# 1-Schematic_Hardware_Space_Systems.net
KiCad netlist of a schematic drawn in EasyEDA
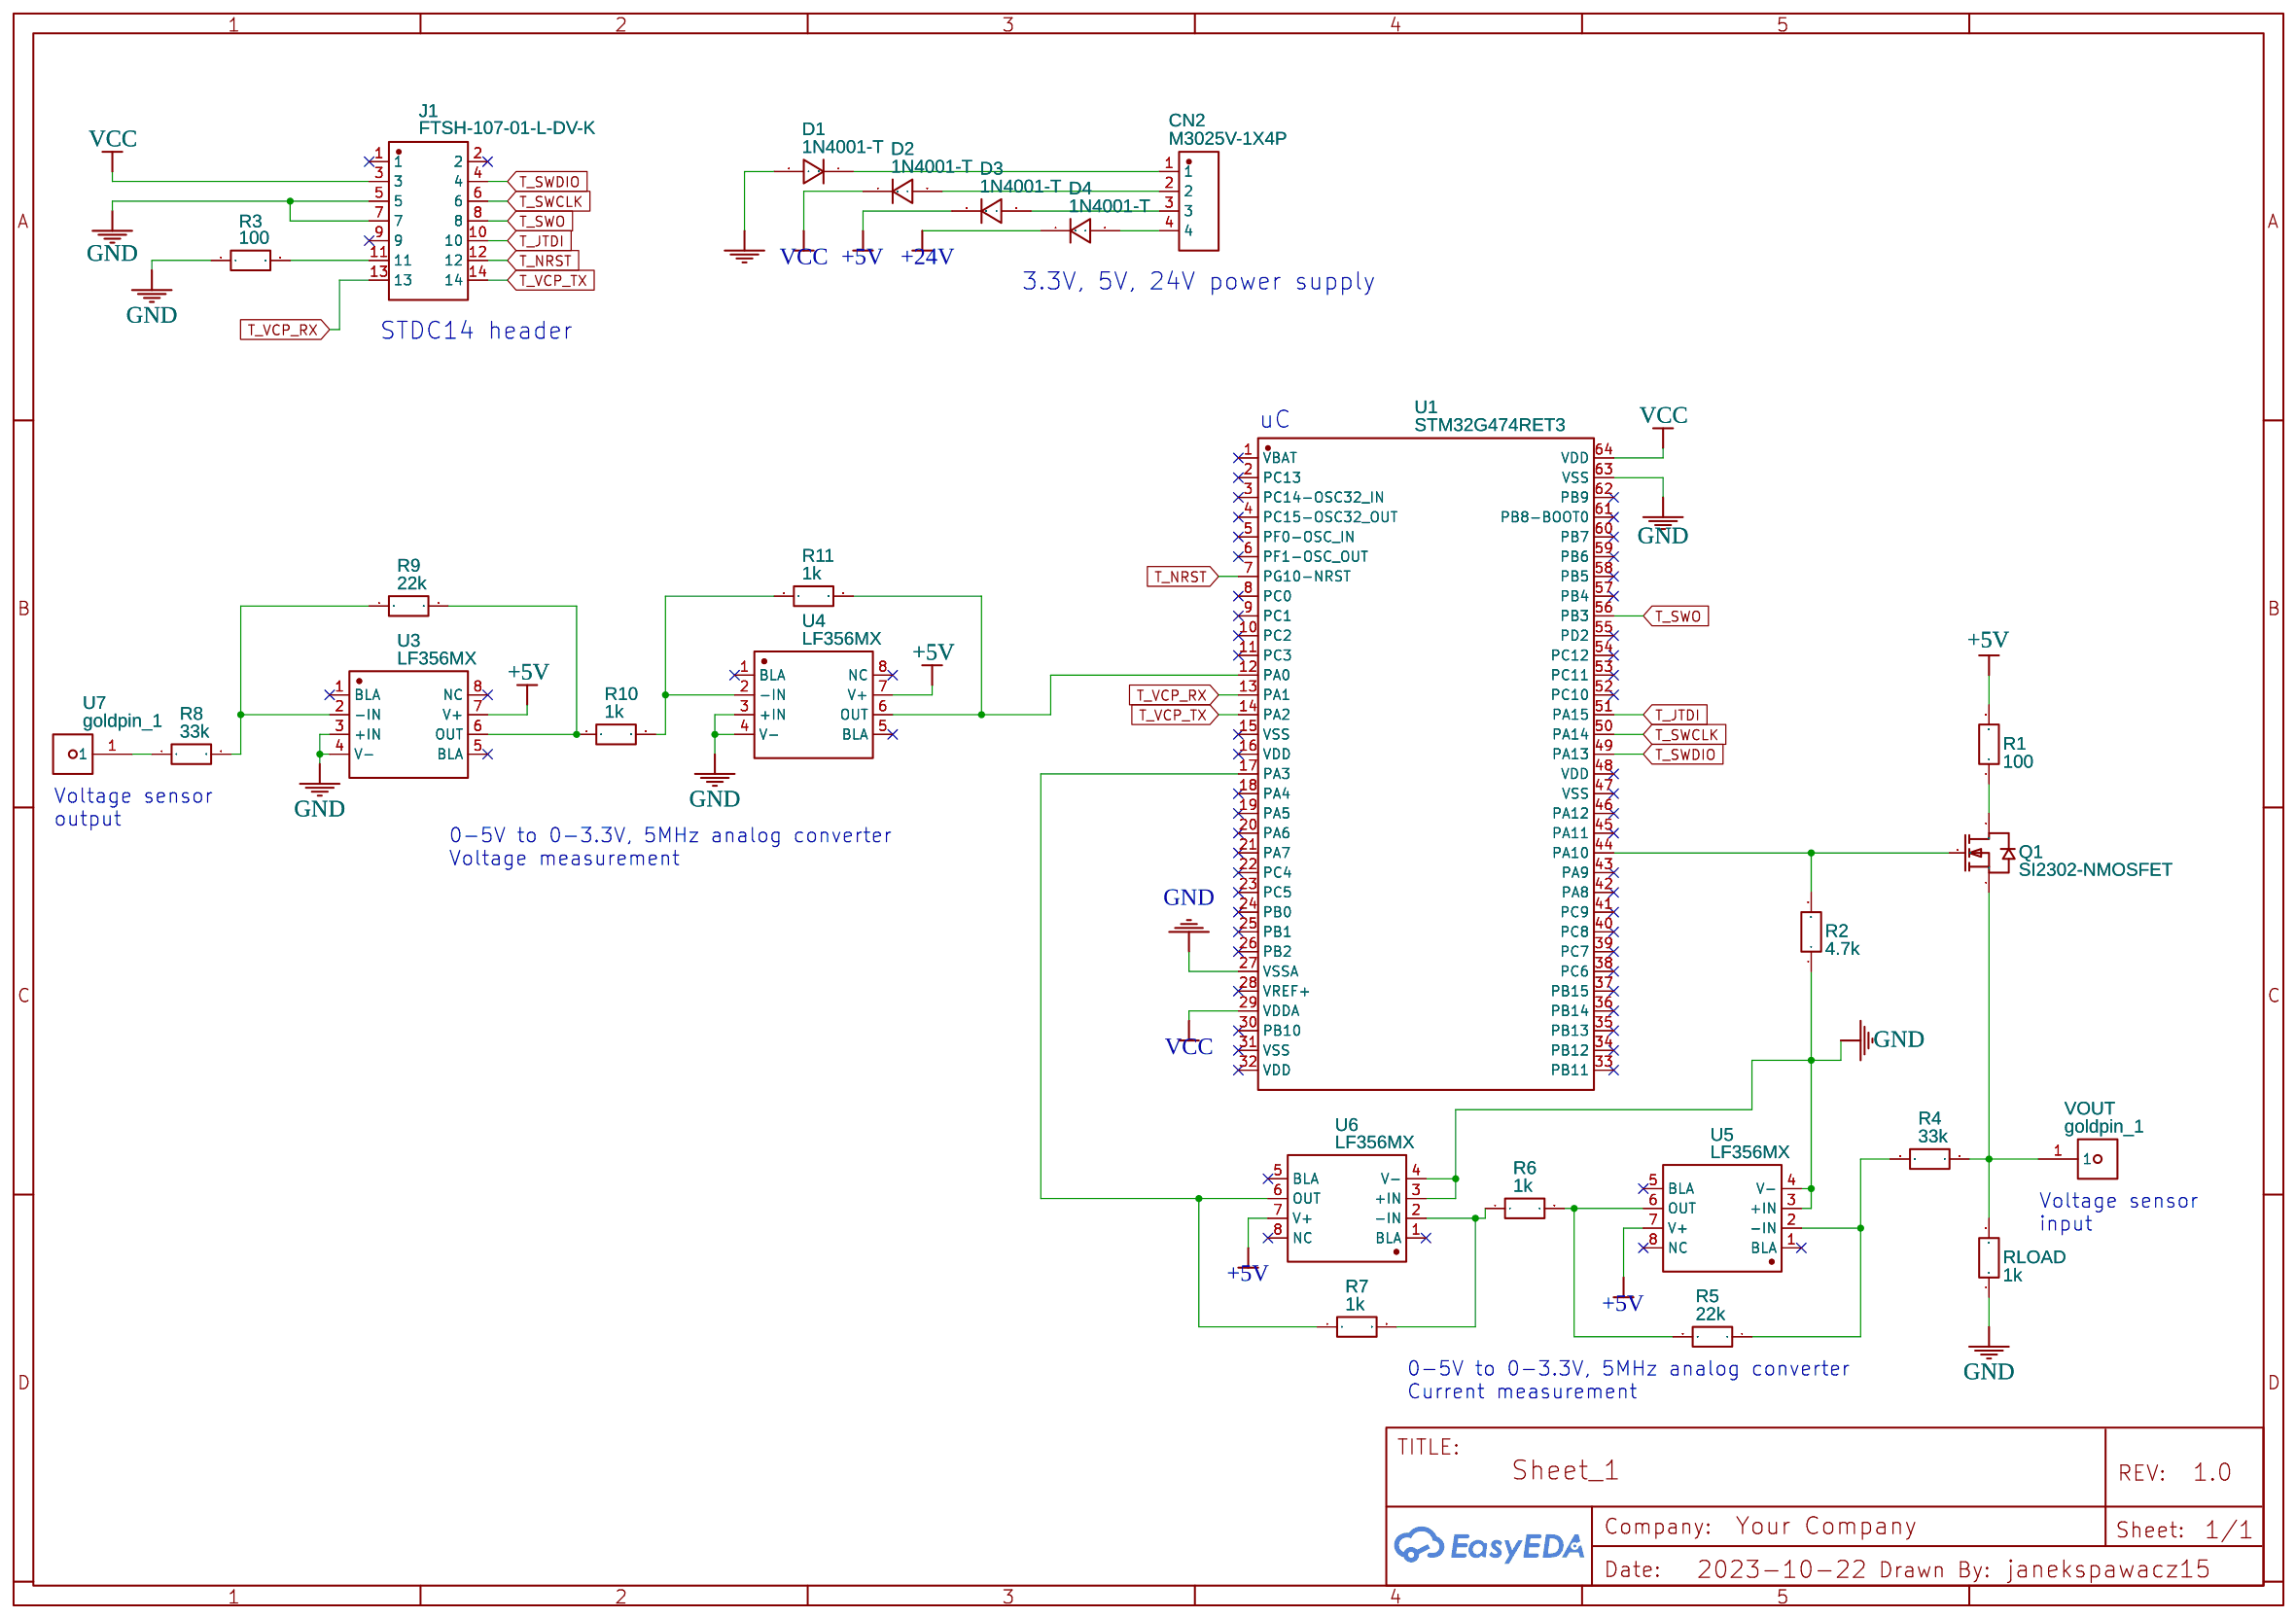
[diagram p0: schematic sheet]

(export (version "E")
  (design (tool "Eeschema 10.0.6"))
  (components
    (comp (ref "CN2")
      (value "M3025V-1X4P")
      (fields (field (name "Manufacturer Part") "M3025V-1x4P") (field (name "Manufacturer") "XFCN(台湾兴飞)"))
      (libsource (lib "") (part "M3025V-1X4P"))
    )
    (comp (ref "D1")
      (value "1N4001-T")
      (fields (field (name "Manufacturer") "DIODES(美台)"))
      (libsource (lib "") (part "1N4001-T_1"))
    )
    (comp (ref "D2")
      (value "1N4001-T")
      (fields (field (name "Manufacturer") "DIODES(美台)"))
      (libsource (lib "") (part "1N4001-T"))
    )
    (comp (ref "D3")
      (value "1N4001-T")
      (fields (field (name "Manufacturer") "DIODES(美台)"))
      (libsource (lib "") (part "1N4001-T"))
    )
    (comp (ref "D4")
      (value "1N4001-T")
      (fields (field (name "Manufacturer") "DIODES(美台)"))
      (libsource (lib "") (part "1N4001-T"))
    )
    (comp (ref "J1")
      (value "FTSH-107-01-L-DV-K")
      (fields (field (name "Manufacturer") "Samtec"))
      (libsource (lib "") (part "FTSH-107-01-L-DV-K"))
    )
    (comp (ref "Q1")
      (value "SI2302-NMOSFET")
      (fields (field (name "Manufacturer Part") "si2302-nmosfet"))
      (libsource (lib "") (part "SI2302-NMOSFET"))
    )
    (comp (ref "R1") (value "100") (libsource (lib "") (part "R_0603_EU_3")))
    (comp (ref "R2") (value "4.7k") (libsource (lib "") (part "R_0603_EU_3")))
    (comp (ref "R3") (value "100") (libsource (lib "") (part "R_0603_EU_1")))
    (comp (ref "R4") (value "33k") (libsource (lib "") (part "R_0603_EU_2")))
    (comp (ref "R5") (value "22k") (libsource (lib "") (part "R_0603_EU_2")))
    (comp (ref "R6") (value "1k") (libsource (lib "") (part "R_0603_EU_1")))
    (comp (ref "R7") (value "1k") (libsource (lib "") (part "R_0603_EU_1")))
    (comp (ref "R8") (value "33k") (libsource (lib "") (part "R_0603_EU_1")))
    (comp (ref "R9") (value "22k") (libsource (lib "") (part "R_0603_EU_1")))
    (comp (ref "R10") (value "1k") (libsource (lib "") (part "R_0603_EU_1")))
    (comp (ref "R11") (value "1k") (libsource (lib "") (part "R_0603_EU_1")))
    (comp (ref "RLOAD") (value "1k") (libsource (lib "") (part "R_0603_EU")))
    (comp (ref "U1")
      (value "STM32G474RET3")
      (fields (field (name "Manufacturer") "ST(意法半导体)"))
      (libsource (lib "") (part "STM32G474RET3"))
    )
    (comp (ref "U3")
      (value "LF356MX")
      (fields (field (name "Manufacturer Part") "LF356MX/NOPB") (field (name "Manufacturer") "TI(德州仪器)"))
      (libsource (lib "") (part "LF356MX"))
    )
    (comp (ref "U4")
      (value "LF356MX")
      (fields (field (name "Manufacturer Part") "LF356MX/NOPB") (field (name "Manufacturer") "TI(德州仪器)"))
      (libsource (lib "") (part "LF356MX"))
    )
    (comp (ref "U5")
      (value "LF356MX")
      (fields (field (name "Manufacturer Part") "LF356MX/NOPB") (field (name "Manufacturer") "TI(德州仪器)"))
      (libsource (lib "") (part "LF356MX_1"))
    )
    (comp (ref "U6")
      (value "LF356MX")
      (fields (field (name "Manufacturer Part") "LF356MX/NOPB") (field (name "Manufacturer") "TI(德州仪器)"))
      (libsource (lib "") (part "LF356MX_1"))
    )
    (comp (ref "U7") (value "goldpin_1") (libsource (lib "") (part "goldpin_1_1")))
    (comp (ref "VOUT") (value "goldpin_1") (libsource (lib "") (part "goldpin_1")))
  )
  (nets
    (net (code "1") (name "+5V") (class "Default")
      (node (ref "D3") (pin "1") (pinfunction "C_1") (pintype "unspecified"))
      (node (ref "R1") (pin "2") (pinfunction "2_2") (pintype "unspecified"))
      (node (ref "U3") (pin "7") (pinfunction "V+_7") (pintype "unspecified"))
      (node (ref "U4") (pin "7") (pinfunction "V+_7") (pintype "unspecified"))
      (node (ref "U5") (pin "7") (pinfunction "V+_7") (pintype "unspecified"))
      (node (ref "U6") (pin "7") (pinfunction "V+_7") (pintype "unspecified"))
    )
    (net (code "2") (name "+24V") (class "Default")
      (node (ref "D4") (pin "1") (pinfunction "C_1") (pintype "unspecified"))
    )
    (net (code "3") (name "GND") (class "Default")
      (node (ref "D1") (pin "2") (pinfunction "A_2") (pintype "unspecified"))
      (node (ref "J1") (pin "5") (pinfunction "5_5") (pintype "unspecified"))
      (node (ref "J1") (pin "7") (pinfunction "7_7") (pintype "unspecified"))
      (node (ref "R2") (pin "1") (pinfunction "1_1") (pintype "unspecified"))
      (node (ref "R3") (pin "1") (pinfunction "1_1") (pintype "unspecified"))
      (node (ref "RLOAD") (pin "1") (pinfunction "1_1") (pintype "unspecified"))
      (node (ref "U1") (pin "27") (pinfunction "VSSA_27") (pintype "unspecified"))
      (node (ref "U1") (pin "63") (pinfunction "VSS_63") (pintype "unspecified"))
      (node (ref "U3") (pin "3") (pinfunction "+IN_3") (pintype "unspecified"))
      (node (ref "U3") (pin "4") (pinfunction "V-_4") (pintype "unspecified"))
      (node (ref "U4") (pin "3") (pinfunction "+IN_3") (pintype "unspecified"))
      (node (ref "U4") (pin "4") (pinfunction "V-_4") (pintype "unspecified"))
      (node (ref "U5") (pin "3") (pinfunction "+IN_3") (pintype "unspecified"))
      (node (ref "U5") (pin "4") (pinfunction "V-_4") (pintype "unspecified"))
      (node (ref "U6") (pin "3") (pinfunction "+IN_3") (pintype "unspecified"))
      (node (ref "U6") (pin "4") (pinfunction "V-_4") (pintype "unspecified"))
    )
    (net (code "4") (name "Net-(D1-C)") (class "Default")
      (node (ref "CN2") (pin "1") (pinfunction "1_1") (pintype "unspecified"))
      (node (ref "D1") (pin "1") (pinfunction "C_1") (pintype "unspecified"))
    )
    (net (code "5") (name "Net-(D2-A)") (class "Default")
      (node (ref "CN2") (pin "2") (pinfunction "2_2") (pintype "unspecified"))
      (node (ref "D2") (pin "2") (pinfunction "A_2") (pintype "unspecified"))
    )
    (net (code "6") (name "Net-(D3-A)") (class "Default")
      (node (ref "CN2") (pin "3") (pinfunction "3_3") (pintype "unspecified"))
      (node (ref "D3") (pin "2") (pinfunction "A_2") (pintype "unspecified"))
    )
    (net (code "7") (name "Net-(D4-A)") (class "Default")
      (node (ref "CN2") (pin "4") (pinfunction "4_4") (pintype "unspecified"))
      (node (ref "D4") (pin "2") (pinfunction "A_2") (pintype "unspecified"))
    )
    (net (code "8") (name "Net-(J1-Pad11)") (class "Default")
      (node (ref "J1") (pin "11") (pinfunction "11_11") (pintype "unspecified"))
      (node (ref "R3") (pin "2") (pinfunction "2_2") (pintype "unspecified"))
    )
    (net (code "9") (name "Net-(Q1-D)") (class "Default")
      (node (ref "Q1") (pin "3") (pinfunction "D_3") (pintype "unspecified"))
      (node (ref "R1") (pin "1") (pinfunction "1_1") (pintype "unspecified"))
    )
    (net (code "10") (name "Net-(Q1-G)") (class "Default")
      (node (ref "Q1") (pin "1") (pinfunction "G_1") (pintype "unspecified"))
      (node (ref "R2") (pin "2") (pinfunction "2_2") (pintype "unspecified"))
      (node (ref "U1") (pin "44") (pinfunction "PA10_44") (pintype "unspecified"))
    )
    (net (code "11") (name "Net-(Q1-S)") (class "Default")
      (node (ref "Q1") (pin "2") (pinfunction "S_2") (pintype "unspecified"))
      (node (ref "R4") (pin "1") (pinfunction "1_1") (pintype "unspecified"))
      (node (ref "RLOAD") (pin "2") (pinfunction "2_2") (pintype "unspecified"))
      (node (ref "VOUT") (pin "1") (pinfunction "1_1") (pintype "unspecified"))
    )
    (net (code "12") (name "Net-(R8-Pad1)") (class "Default")
      (node (ref "R8") (pin "1") (pinfunction "1_1") (pintype "unspecified"))
      (node (ref "U7") (pin "1") (pinfunction "1_1") (pintype "unspecified"))
    )
    (net (code "13") (name "Net-(U1-PA0)") (class "Default")
      (node (ref "R11") (pin "2") (pinfunction "2_2") (pintype "unspecified"))
      (node (ref "U1") (pin "12") (pinfunction "PA0_12") (pintype "unspecified"))
      (node (ref "U4") (pin "6") (pinfunction "OUT_6") (pintype "unspecified"))
    )
    (net (code "14") (name "Net-(U1-PA3)") (class "Default")
      (node (ref "R7") (pin "1") (pinfunction "1_1") (pintype "unspecified"))
      (node (ref "U1") (pin "17") (pinfunction "PA3_17") (pintype "unspecified"))
      (node (ref "U6") (pin "6") (pinfunction "OUT_6") (pintype "unspecified"))
    )
    (net (code "15") (name "Net-(U3--IN)") (class "Default")
      (node (ref "R8") (pin "2") (pinfunction "2_2") (pintype "unspecified"))
      (node (ref "R9") (pin "1") (pinfunction "1_1") (pintype "unspecified"))
      (node (ref "U3") (pin "2") (pinfunction "-IN_2") (pintype "unspecified"))
    )
    (net (code "16") (name "Net-(U3-OUT)") (class "Default")
      (node (ref "R10") (pin "1") (pinfunction "1_1") (pintype "unspecified"))
      (node (ref "R9") (pin "2") (pinfunction "2_2") (pintype "unspecified"))
      (node (ref "U3") (pin "6") (pinfunction "OUT_6") (pintype "unspecified"))
    )
    (net (code "17") (name "Net-(U4--IN)") (class "Default")
      (node (ref "R10") (pin "2") (pinfunction "2_2") (pintype "unspecified"))
      (node (ref "R11") (pin "1") (pinfunction "1_1") (pintype "unspecified"))
      (node (ref "U4") (pin "2") (pinfunction "-IN_2") (pintype "unspecified"))
    )
    (net (code "18") (name "Net-(U5--IN)") (class "Default")
      (node (ref "R4") (pin "2") (pinfunction "2_2") (pintype "unspecified"))
      (node (ref "R5") (pin "1") (pinfunction "1_1") (pintype "unspecified"))
      (node (ref "U5") (pin "2") (pinfunction "-IN_2") (pintype "unspecified"))
    )
    (net (code "19") (name "Net-(U5-OUT)") (class "Default")
      (node (ref "R5") (pin "2") (pinfunction "2_2") (pintype "unspecified"))
      (node (ref "R6") (pin "2") (pinfunction "2_2") (pintype "unspecified"))
      (node (ref "U5") (pin "6") (pinfunction "OUT_6") (pintype "unspecified"))
    )
    (net (code "20") (name "Net-(U6--IN)") (class "Default")
      (node (ref "R6") (pin "1") (pinfunction "1_1") (pintype "unspecified"))
      (node (ref "R7") (pin "2") (pinfunction "2_2") (pintype "unspecified"))
      (node (ref "U6") (pin "2") (pinfunction "-IN_2") (pintype "unspecified"))
    )
    (net (code "21") (name "T_JTDI") (class "Default")
      (node (ref "J1") (pin "10") (pinfunction "10_10") (pintype "unspecified"))
      (node (ref "U1") (pin "51") (pinfunction "PA15_51") (pintype "unspecified"))
    )
    (net (code "22") (name "T_NRST") (class "Default")
      (node (ref "J1") (pin "12") (pinfunction "12_12") (pintype "unspecified"))
      (node (ref "U1") (pin "7") (pinfunction "PG10-NRST_7") (pintype "unspecified"))
    )
    (net (code "23") (name "T_SWCLK") (class "Default")
      (node (ref "J1") (pin "6") (pinfunction "6_6") (pintype "unspecified"))
      (node (ref "U1") (pin "50") (pinfunction "PA14_50") (pintype "unspecified"))
    )
    (net (code "24") (name "T_SWDIO") (class "Default")
      (node (ref "J1") (pin "4") (pinfunction "4_4") (pintype "unspecified"))
      (node (ref "U1") (pin "49") (pinfunction "PA13_49") (pintype "unspecified"))
    )
    (net (code "25") (name "T_SWO") (class "Default")
      (node (ref "J1") (pin "8") (pinfunction "8_8") (pintype "unspecified"))
      (node (ref "U1") (pin "56") (pinfunction "PB3_56") (pintype "unspecified"))
    )
    (net (code "26") (name "T_VCP_RX") (class "Default")
      (node (ref "J1") (pin "13") (pinfunction "13_13") (pintype "unspecified"))
      (node (ref "U1") (pin "13") (pinfunction "PA1_13") (pintype "unspecified"))
    )
    (net (code "27") (name "T_VCP_TX") (class "Default")
      (node (ref "J1") (pin "14") (pinfunction "14_14") (pintype "unspecified"))
      (node (ref "U1") (pin "14") (pinfunction "PA2_14") (pintype "unspecified"))
    )
    (net (code "28") (name "VCC") (class "Default")
      (node (ref "D2") (pin "1") (pinfunction "C_1") (pintype "unspecified"))
      (node (ref "J1") (pin "3") (pinfunction "3_3") (pintype "unspecified"))
      (node (ref "U1") (pin "29") (pinfunction "VDDA_29") (pintype "unspecified"))
      (node (ref "U1") (pin "64") (pinfunction "VDD_64") (pintype "unspecified"))
    )
    (net (code "29") (name "unconnected-(J1-Pad1)") (class "Default")
      (node (ref "J1") (pin "1") (pinfunction "1_1") (pintype "unspecified+no_connect"))
    )
    (net (code "30") (name "unconnected-(J1-Pad2)") (class "Default")
      (node (ref "J1") (pin "2") (pinfunction "2_2") (pintype "unspecified+no_connect"))
    )
    (net (code "31") (name "unconnected-(J1-Pad9)") (class "Default")
      (node (ref "J1") (pin "9") (pinfunction "9_9") (pintype "unspecified+no_connect"))
    )
    (net (code "32") (name "unconnected-(U1-PA4-Pad18)") (class "Default")
      (node (ref "U1") (pin "18") (pinfunction "PA4_18") (pintype "unspecified+no_connect"))
    )
    (net (code "33") (name "unconnected-(U1-PA5-Pad19)") (class "Default")
      (node (ref "U1") (pin "19") (pinfunction "PA5_19") (pintype "unspecified+no_connect"))
    )
    (net (code "34") (name "unconnected-(U1-PA6-Pad20)") (class "Default")
      (node (ref "U1") (pin "20") (pinfunction "PA6_20") (pintype "unspecified+no_connect"))
    )
    (net (code "35") (name "unconnected-(U1-PA7-Pad21)") (class "Default")
      (node (ref "U1") (pin "21") (pinfunction "PA7_21") (pintype "unspecified+no_connect"))
    )
    (net (code "36") (name "unconnected-(U1-PA8-Pad42)") (class "Default")
      (node (ref "U1") (pin "42") (pinfunction "PA8_42") (pintype "unspecified+no_connect"))
    )
    (net (code "37") (name "unconnected-(U1-PA9-Pad43)") (class "Default")
      (node (ref "U1") (pin "43") (pinfunction "PA9_43") (pintype "unspecified+no_connect"))
    )
    (net (code "38") (name "unconnected-(U1-PA11-Pad45)") (class "Default")
      (node (ref "U1") (pin "45") (pinfunction "PA11_45") (pintype "unspecified+no_connect"))
    )
    (net (code "39") (name "unconnected-(U1-PA12-Pad46)") (class "Default")
      (node (ref "U1") (pin "46") (pinfunction "PA12_46") (pintype "unspecified+no_connect"))
    )
    (net (code "40") (name "unconnected-(U1-PB0-Pad24)") (class "Default")
      (node (ref "U1") (pin "24") (pinfunction "PB0_24") (pintype "unspecified+no_connect"))
    )
    (net (code "41") (name "unconnected-(U1-PB1-Pad25)") (class "Default")
      (node (ref "U1") (pin "25") (pinfunction "PB1_25") (pintype "unspecified+no_connect"))
    )
    (net (code "42") (name "unconnected-(U1-PB2-Pad26)") (class "Default")
      (node (ref "U1") (pin "26") (pinfunction "PB2_26") (pintype "unspecified+no_connect"))
    )
    (net (code "43") (name "unconnected-(U1-PB4-Pad57)") (class "Default")
      (node (ref "U1") (pin "57") (pinfunction "PB4_57") (pintype "unspecified+no_connect"))
    )
    (net (code "44") (name "unconnected-(U1-PB5-Pad58)") (class "Default")
      (node (ref "U1") (pin "58") (pinfunction "PB5_58") (pintype "unspecified+no_connect"))
    )
    (net (code "45") (name "unconnected-(U1-PB6-Pad59)") (class "Default")
      (node (ref "U1") (pin "59") (pinfunction "PB6_59") (pintype "unspecified+no_connect"))
    )
    (net (code "46") (name "unconnected-(U1-PB7-Pad60)") (class "Default")
      (node (ref "U1") (pin "60") (pinfunction "PB7_60") (pintype "unspecified+no_connect"))
    )
    (net (code "47") (name "unconnected-(U1-PB8-BOOT0-Pad61)") (class "Default")
      (node (ref "U1") (pin "61") (pinfunction "PB8-BOOT0_61") (pintype "unspecified+no_connect"))
    )
    (net (code "48") (name "unconnected-(U1-PB9-Pad62)") (class "Default")
      (node (ref "U1") (pin "62") (pinfunction "PB9_62") (pintype "unspecified+no_connect"))
    )
    (net (code "49") (name "unconnected-(U1-PB10-Pad30)") (class "Default")
      (node (ref "U1") (pin "30") (pinfunction "PB10_30") (pintype "unspecified+no_connect"))
    )
    (net (code "50") (name "unconnected-(U1-PB11-Pad33)") (class "Default")
      (node (ref "U1") (pin "33") (pinfunction "PB11_33") (pintype "unspecified+no_connect"))
    )
    (net (code "51") (name "unconnected-(U1-PB12-Pad34)") (class "Default")
      (node (ref "U1") (pin "34") (pinfunction "PB12_34") (pintype "unspecified+no_connect"))
    )
    (net (code "52") (name "unconnected-(U1-PB13-Pad35)") (class "Default")
      (node (ref "U1") (pin "35") (pinfunction "PB13_35") (pintype "unspecified+no_connect"))
    )
    (net (code "53") (name "unconnected-(U1-PB14-Pad36)") (class "Default")
      (node (ref "U1") (pin "36") (pinfunction "PB14_36") (pintype "unspecified+no_connect"))
    )
    (net (code "54") (name "unconnected-(U1-PB15-Pad37)") (class "Default")
      (node (ref "U1") (pin "37") (pinfunction "PB15_37") (pintype "unspecified+no_connect"))
    )
    (net (code "55") (name "unconnected-(U1-PC0-Pad8)") (class "Default")
      (node (ref "U1") (pin "8") (pinfunction "PC0_8") (pintype "unspecified+no_connect"))
    )
    (net (code "56") (name "unconnected-(U1-PC1-Pad9)") (class "Default")
      (node (ref "U1") (pin "9") (pinfunction "PC1_9") (pintype "unspecified+no_connect"))
    )
    (net (code "57") (name "unconnected-(U1-PC2-Pad10)") (class "Default")
      (node (ref "U1") (pin "10") (pinfunction "PC2_10") (pintype "unspecified+no_connect"))
    )
    (net (code "58") (name "unconnected-(U1-PC3-Pad11)") (class "Default")
      (node (ref "U1") (pin "11") (pinfunction "PC3_11") (pintype "unspecified+no_connect"))
    )
    (net (code "59") (name "unconnected-(U1-PC4-Pad22)") (class "Default")
      (node (ref "U1") (pin "22") (pinfunction "PC4_22") (pintype "unspecified+no_connect"))
    )
    (net (code "60") (name "unconnected-(U1-PC5-Pad23)") (class "Default")
      (node (ref "U1") (pin "23") (pinfunction "PC5_23") (pintype "unspecified+no_connect"))
    )
    (net (code "61") (name "unconnected-(U1-PC6-Pad38)") (class "Default")
      (node (ref "U1") (pin "38") (pinfunction "PC6_38") (pintype "unspecified+no_connect"))
    )
    (net (code "62") (name "unconnected-(U1-PC7-Pad39)") (class "Default")
      (node (ref "U1") (pin "39") (pinfunction "PC7_39") (pintype "unspecified+no_connect"))
    )
    (net (code "63") (name "unconnected-(U1-PC8-Pad40)") (class "Default")
      (node (ref "U1") (pin "40") (pinfunction "PC8_40") (pintype "unspecified+no_connect"))
    )
    (net (code "64") (name "unconnected-(U1-PC9-Pad41)") (class "Default")
      (node (ref "U1") (pin "41") (pinfunction "PC9_41") (pintype "unspecified+no_connect"))
    )
    (net (code "65") (name "unconnected-(U1-PC10-Pad52)") (class "Default")
      (node (ref "U1") (pin "52") (pinfunction "PC10_52") (pintype "unspecified+no_connect"))
    )
    (net (code "66") (name "unconnected-(U1-PC11-Pad53)") (class "Default")
      (node (ref "U1") (pin "53") (pinfunction "PC11_53") (pintype "unspecified+no_connect"))
    )
    (net (code "67") (name "unconnected-(U1-PC12-Pad54)") (class "Default")
      (node (ref "U1") (pin "54") (pinfunction "PC12_54") (pintype "unspecified+no_connect"))
    )
    (net (code "68") (name "unconnected-(U1-PC13-Pad2)") (class "Default")
      (node (ref "U1") (pin "2") (pinfunction "PC13_2") (pintype "unspecified+no_connect"))
    )
    (net (code "69") (name "unconnected-(U1-PC14-OSC32_IN-Pad3)") (class "Default")
      (node (ref "U1") (pin "3") (pinfunction "PC14-OSC32_IN_3") (pintype "unspecified+no_connect"))
    )
    (net (code "70") (name "unconnected-(U1-PC15-OSC32_OUT-Pad4)") (class "Default")
      (node (ref "U1") (pin "4") (pinfunction "PC15-OSC32_OUT_4") (pintype "unspecified+no_connect"))
    )
    (net (code "71") (name "unconnected-(U1-PD2-Pad55)") (class "Default")
      (node (ref "U1") (pin "55") (pinfunction "PD2_55") (pintype "unspecified+no_connect"))
    )
    (net (code "72") (name "unconnected-(U1-PF0-OSC_IN-Pad5)") (class "Default")
      (node (ref "U1") (pin "5") (pinfunction "PF0-OSC_IN_5") (pintype "unspecified+no_connect"))
    )
    (net (code "73") (name "unconnected-(U1-PF1-OSC_OUT-Pad6)") (class "Default")
      (node (ref "U1") (pin "6") (pinfunction "PF1-OSC_OUT_6") (pintype "unspecified+no_connect"))
    )
    (net (code "74") (name "unconnected-(U1-VBAT-Pad1)") (class "Default")
      (node (ref "U1") (pin "1") (pinfunction "VBAT_1") (pintype "unspecified+no_connect"))
    )
    (net (code "75") (name "unconnected-(U1-VDD-Pad16)") (class "Default")
      (node (ref "U1") (pin "16") (pinfunction "VDD_16") (pintype "unspecified+no_connect"))
    )
    (net (code "76") (name "unconnected-(U1-VDD-Pad32)") (class "Default")
      (node (ref "U1") (pin "32") (pinfunction "VDD_32") (pintype "unspecified+no_connect"))
    )
    (net (code "77") (name "unconnected-(U1-VDD-Pad48)") (class "Default")
      (node (ref "U1") (pin "48") (pinfunction "VDD_48") (pintype "unspecified+no_connect"))
    )
    (net (code "78") (name "unconnected-(U1-VREF+-Pad28)") (class "Default")
      (node (ref "U1") (pin "28") (pinfunction "VREF+_28") (pintype "unspecified+no_connect"))
    )
    (net (code "79") (name "unconnected-(U1-VSS-Pad15)") (class "Default")
      (node (ref "U1") (pin "15") (pinfunction "VSS_15") (pintype "unspecified+no_connect"))
    )
    (net (code "80") (name "unconnected-(U1-VSS-Pad31)") (class "Default")
      (node (ref "U1") (pin "31") (pinfunction "VSS_31") (pintype "unspecified+no_connect"))
    )
    (net (code "81") (name "unconnected-(U1-VSS-Pad47)") (class "Default")
      (node (ref "U1") (pin "47") (pinfunction "VSS_47") (pintype "unspecified+no_connect"))
    )
    (net (code "82") (name "unconnected-(U3-BLA-Pad1)") (class "Default")
      (node (ref "U3") (pin "1") (pinfunction "BLA_1") (pintype "unspecified+no_connect"))
    )
    (net (code "83") (name "unconnected-(U3-BLA-Pad5)") (class "Default")
      (node (ref "U3") (pin "5") (pinfunction "BLA_5") (pintype "unspecified+no_connect"))
    )
    (net (code "84") (name "unconnected-(U3-NC-Pad8)") (class "Default")
      (node (ref "U3") (pin "8") (pinfunction "NC_8") (pintype "unspecified+no_connect"))
    )
    (net (code "85") (name "unconnected-(U4-BLA-Pad1)") (class "Default")
      (node (ref "U4") (pin "1") (pinfunction "BLA_1") (pintype "unspecified+no_connect"))
    )
    (net (code "86") (name "unconnected-(U4-BLA-Pad5)") (class "Default")
      (node (ref "U4") (pin "5") (pinfunction "BLA_5") (pintype "unspecified+no_connect"))
    )
    (net (code "87") (name "unconnected-(U4-NC-Pad8)") (class "Default")
      (node (ref "U4") (pin "8") (pinfunction "NC_8") (pintype "unspecified+no_connect"))
    )
    (net (code "88") (name "unconnected-(U5-BLA-Pad1)") (class "Default")
      (node (ref "U5") (pin "1") (pinfunction "BLA_1") (pintype "unspecified+no_connect"))
    )
    (net (code "89") (name "unconnected-(U5-BLA-Pad5)") (class "Default")
      (node (ref "U5") (pin "5") (pinfunction "BLA_5") (pintype "unspecified+no_connect"))
    )
    (net (code "90") (name "unconnected-(U5-NC-Pad8)") (class "Default")
      (node (ref "U5") (pin "8") (pinfunction "NC_8") (pintype "unspecified+no_connect"))
    )
    (net (code "91") (name "unconnected-(U6-BLA-Pad1)") (class "Default")
      (node (ref "U6") (pin "1") (pinfunction "BLA_1") (pintype "unspecified+no_connect"))
    )
    (net (code "92") (name "unconnected-(U6-BLA-Pad5)") (class "Default")
      (node (ref "U6") (pin "5") (pinfunction "BLA_5") (pintype "unspecified+no_connect"))
    )
    (net (code "93") (name "unconnected-(U6-NC-Pad8)") (class "Default")
      (node (ref "U6") (pin "8") (pinfunction "NC_8") (pintype "unspecified+no_connect"))
    )
  )
)
